# SCH_Orion_Power_Supply_2023-01-06.net
KiCad netlist of a schematic drawn in EasyEDA
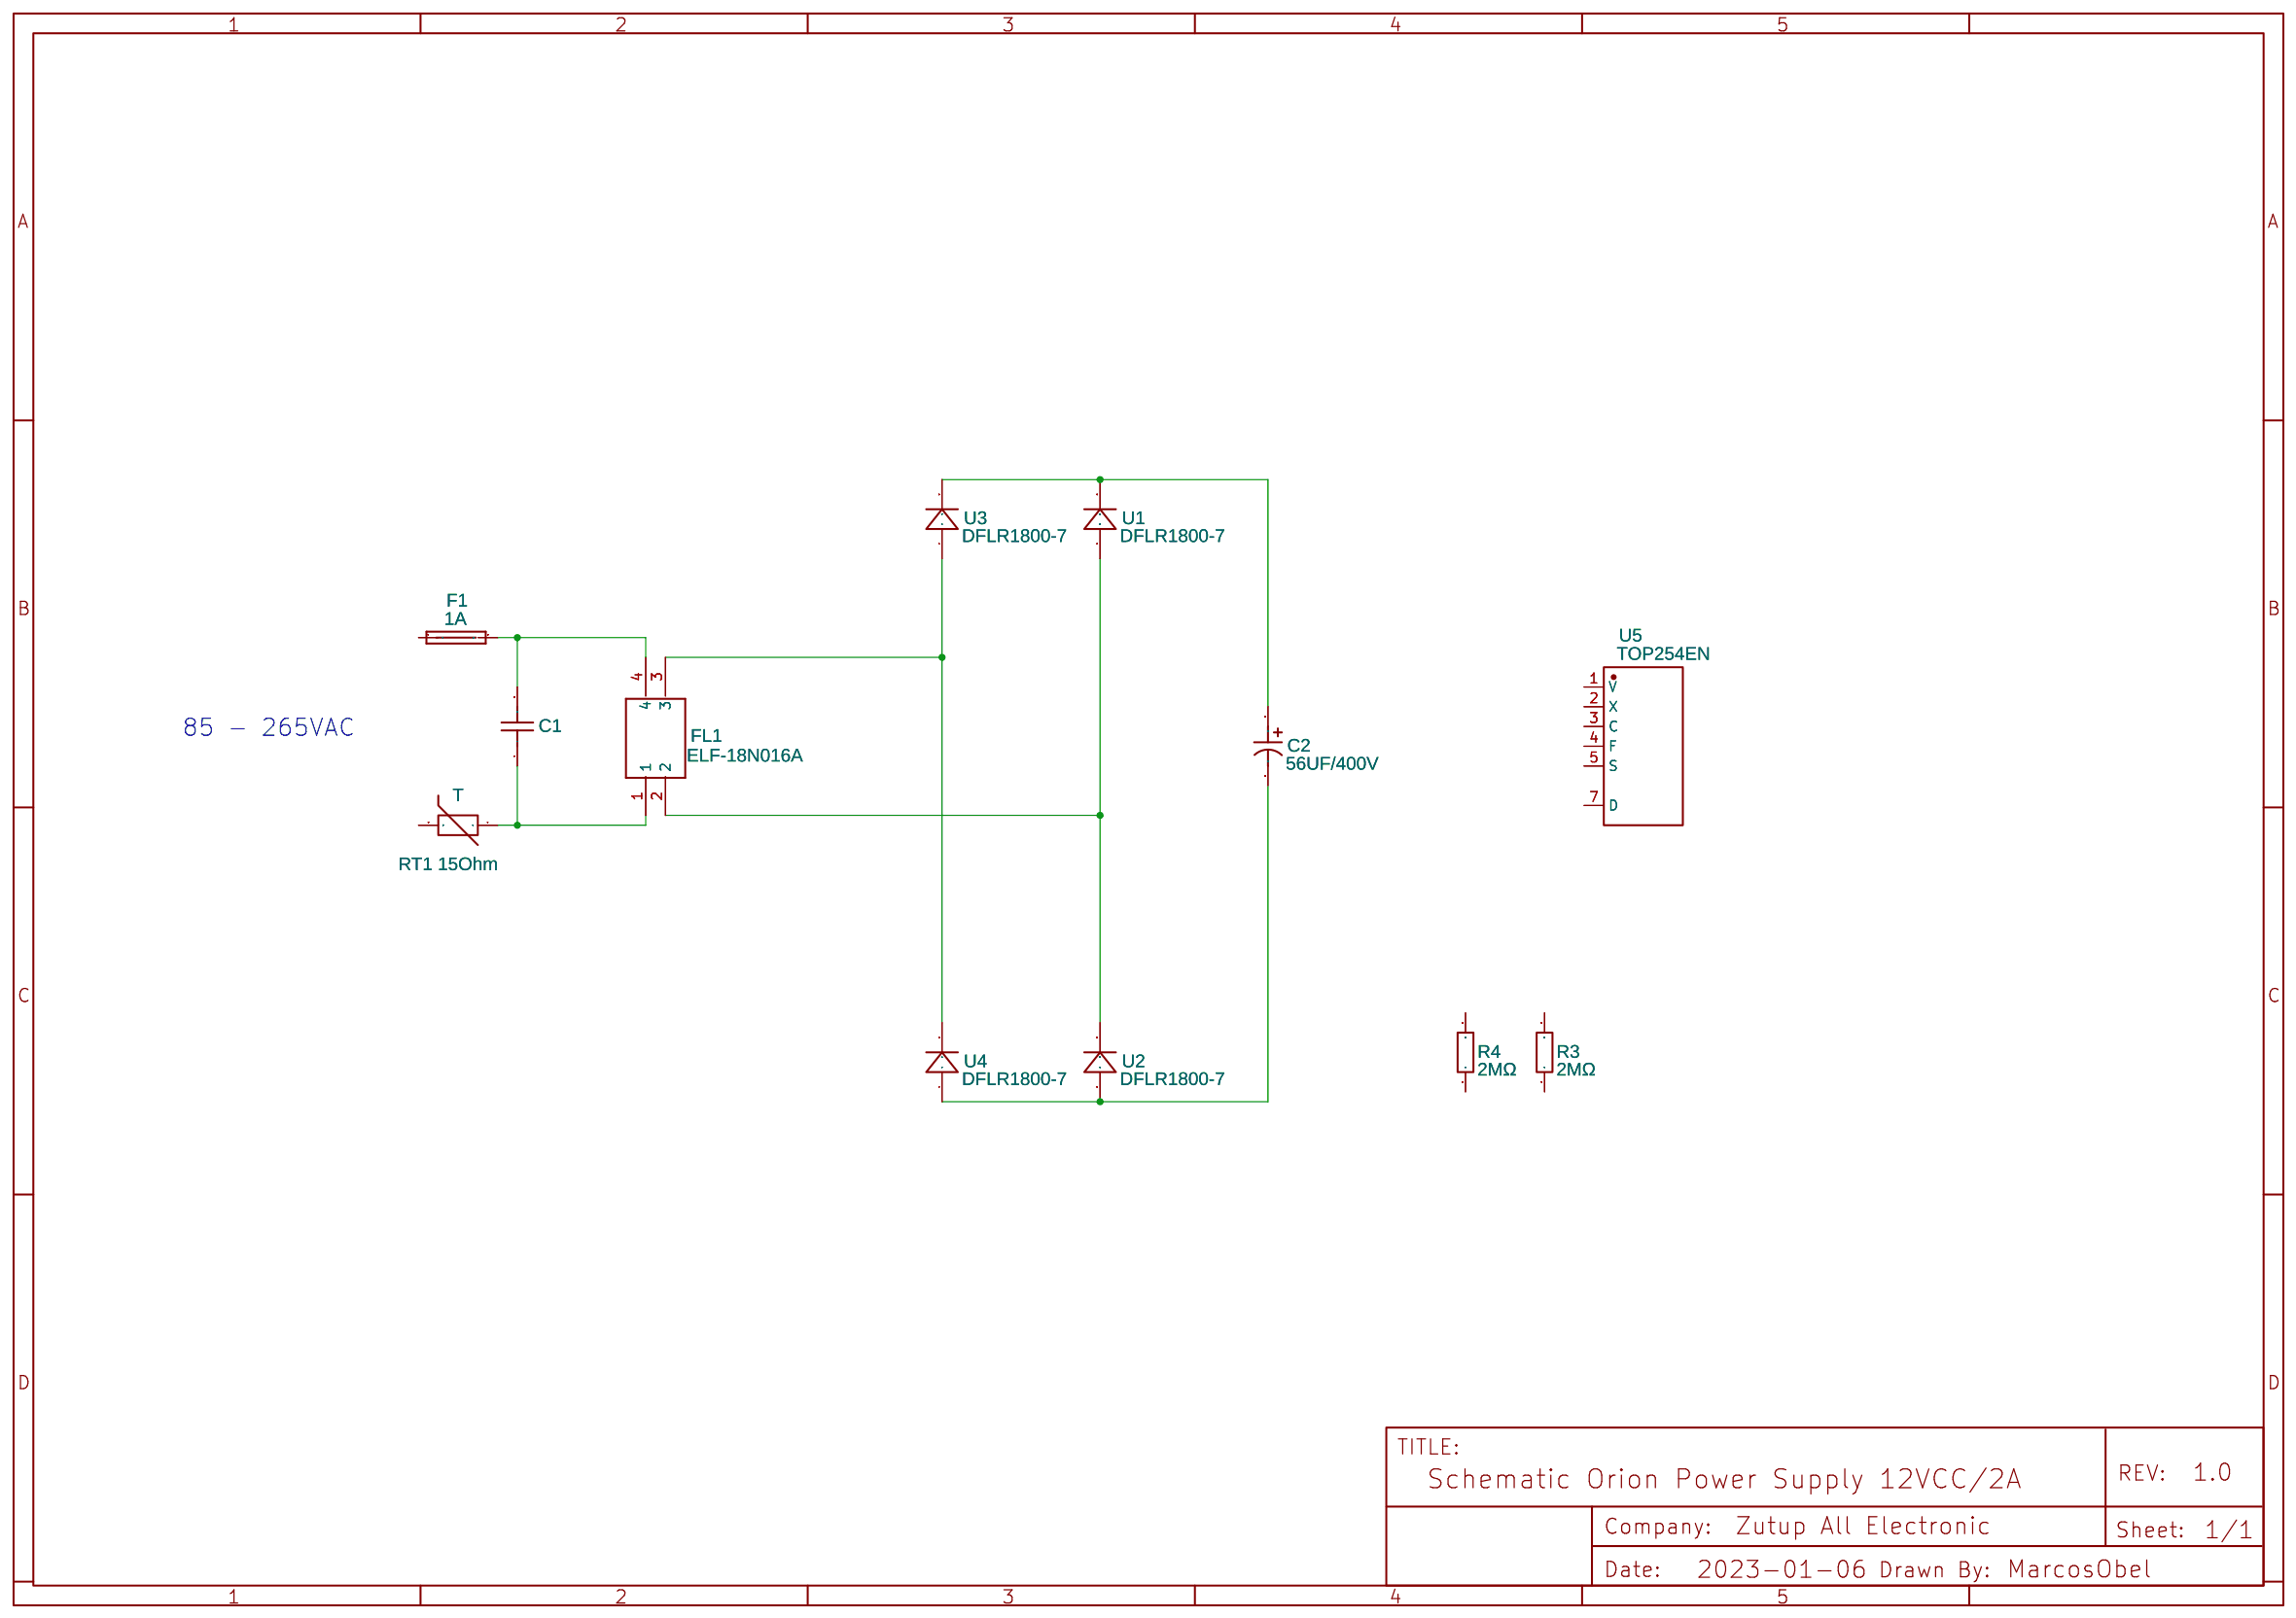
[diagram p0: schematic sheet]

(export (version "E")
  (design (tool "Eeschema 10.0.6"))
  (components
    (comp (ref "C1")
      (value "C212G473K3AC000")
      (fields (field (name "BOM_Supplier Part") "C3025105"))
      (libsource (lib "") (part "C212G473K3AC000"))
    )
    (comp (ref "C2")
      (value "56UF/400V")
      (fields
        (field (name "BOM_Manufacturer Part") "47uF/400V")
        (field (name "BOM_Supplier Part") "C9900023263")
      )
      (libsource (lib "") (part "47UF/400V"))
    )
    (comp (ref "F1") (value "1A") (libsource (lib "") (part "FUSE HOLDER PANJANG")))
    (comp (ref "FL1") (value "ELF-18N016A") (libsource (lib "") (part "ELF-18N016A")))
    (comp (ref "R3")
      (value "2MΩ")
      (fields
        (field (name "BOM_Manufacturer Part") "MHR0314SA207F70")
        (field (name "BOM_Supplier Part") "C116786")
      )
      (libsource (lib "") (part "MHR0314SA207F70"))
    )
    (comp (ref "R4")
      (value "2MΩ")
      (fields
        (field (name "BOM_Manufacturer Part") "MHR0314SA207F70")
        (field (name "BOM_Supplier Part") "C116786")
      )
      (libsource (lib "") (part "MHR0314SA207F70"))
    )
    (comp (ref "T") (value "RT1 15Ohm") (libsource (lib "") (part "TERMISTOR")))
    (comp (ref "U1") (value "DFLR1800-7") (libsource (lib "") (part "DFLR1800-7")))
    (comp (ref "U2") (value "DFLR1800-7") (libsource (lib "") (part "DFLR1800-7")))
    (comp (ref "U3") (value "DFLR1800-7") (libsource (lib "") (part "DFLR1800-7")))
    (comp (ref "U4") (value "DFLR1800-7") (libsource (lib "") (part "DFLR1800-7")))
    (comp (ref "U5")
      (value "TOP254EN")
      (fields (field (name "BOM_Supplier Part") "C568146"))
      (libsource (lib "") (part "TOP254EN"))
    )
  )
  (nets
    (net (code "1") (name "Net-(C1-Pad1)") (class "Default")
      (node (ref "C1") (pin "1") (pinfunction "1_1") (pintype "unspecified"))
      (node (ref "FL1") (pin "1") (pinfunction "1_1") (pintype "bidirectional"))
      (node (ref "T") (pin "1") (pinfunction "1_1") (pintype "unspecified"))
    )
    (net (code "2") (name "Net-(C1-Pad2)") (class "Default")
      (node (ref "C1") (pin "2") (pinfunction "2_2") (pintype "unspecified"))
      (node (ref "F1") (pin "2") (pinfunction "2_2") (pintype "bidirectional"))
      (node (ref "FL1") (pin "4") (pinfunction "4_4") (pintype "bidirectional"))
    )
    (net (code "3") (name "Net-(C2-Pad1)") (class "Default")
      (node (ref "C2") (pin "1") (pinfunction "1_1") (pintype "input"))
      (node (ref "U1") (pin "2") (pinfunction "2_2") (pintype "unspecified"))
      (node (ref "U3") (pin "2") (pinfunction "2_2") (pintype "unspecified"))
    )
    (net (code "4") (name "Net-(C2-Pad2)") (class "Default")
      (node (ref "C2") (pin "2") (pinfunction "2_2") (pintype "input"))
      (node (ref "U2") (pin "1") (pinfunction "1_1") (pintype "unspecified"))
      (node (ref "U4") (pin "1") (pinfunction "1_1") (pintype "unspecified"))
    )
    (net (code "5") (name "Net-(FL1-Pad2)") (class "Default")
      (node (ref "FL1") (pin "2") (pinfunction "2_2") (pintype "bidirectional"))
      (node (ref "U1") (pin "1") (pinfunction "1_1") (pintype "unspecified"))
      (node (ref "U2") (pin "2") (pinfunction "2_2") (pintype "unspecified"))
    )
    (net (code "6") (name "Net-(FL1-Pad3)") (class "Default")
      (node (ref "FL1") (pin "3") (pinfunction "3_3") (pintype "bidirectional"))
      (node (ref "U3") (pin "1") (pinfunction "1_1") (pintype "unspecified"))
      (node (ref "U4") (pin "2") (pinfunction "2_2") (pintype "unspecified"))
    )
    (net (code "7") (name "unconnected-(F1-Pad1)") (class "Default")
      (node (ref "F1") (pin "1") (pinfunction "1_1") (pintype "bidirectional"))
    )
    (net (code "8") (name "unconnected-(R3-Pad1)") (class "Default")
      (node (ref "R3") (pin "1") (pinfunction "1_1") (pintype "unspecified"))
    )
    (net (code "9") (name "unconnected-(R3-Pad2)") (class "Default")
      (node (ref "R3") (pin "2") (pinfunction "2_2") (pintype "unspecified"))
    )
    (net (code "10") (name "unconnected-(R4-Pad1)") (class "Default")
      (node (ref "R4") (pin "1") (pinfunction "1_1") (pintype "unspecified"))
    )
    (net (code "11") (name "unconnected-(R4-Pad2)") (class "Default")
      (node (ref "R4") (pin "2") (pinfunction "2_2") (pintype "unspecified"))
    )
    (net (code "12") (name "unconnected-(T-Pad2)") (class "Default")
      (node (ref "T") (pin "2") (pinfunction "2_2") (pintype "unspecified"))
    )
    (net (code "13") (name "unconnected-(U5-C-Pad3)") (class "Default")
      (node (ref "U5") (pin "3") (pinfunction "C_3") (pintype "unspecified"))
    )
    (net (code "14") (name "unconnected-(U5-D-Pad7)") (class "Default")
      (node (ref "U5") (pin "7") (pinfunction "D_7") (pintype "unspecified"))
    )
    (net (code "15") (name "unconnected-(U5-F-Pad4)") (class "Default")
      (node (ref "U5") (pin "4") (pinfunction "F_4") (pintype "unspecified"))
    )
    (net (code "16") (name "unconnected-(U5-S-Pad5)") (class "Default")
      (node (ref "U5") (pin "5") (pinfunction "S_5") (pintype "unspecified"))
    )
    (net (code "17") (name "unconnected-(U5-V-Pad1)") (class "Default")
      (node (ref "U5") (pin "1") (pinfunction "V_1") (pintype "unspecified"))
    )
    (net (code "18") (name "unconnected-(U5-X-Pad2)") (class "Default")
      (node (ref "U5") (pin "2") (pinfunction "X_2") (pintype "unspecified"))
    )
  )
)
